# streifen.net
KiCad netlist of a schematic drawn in EAGLE
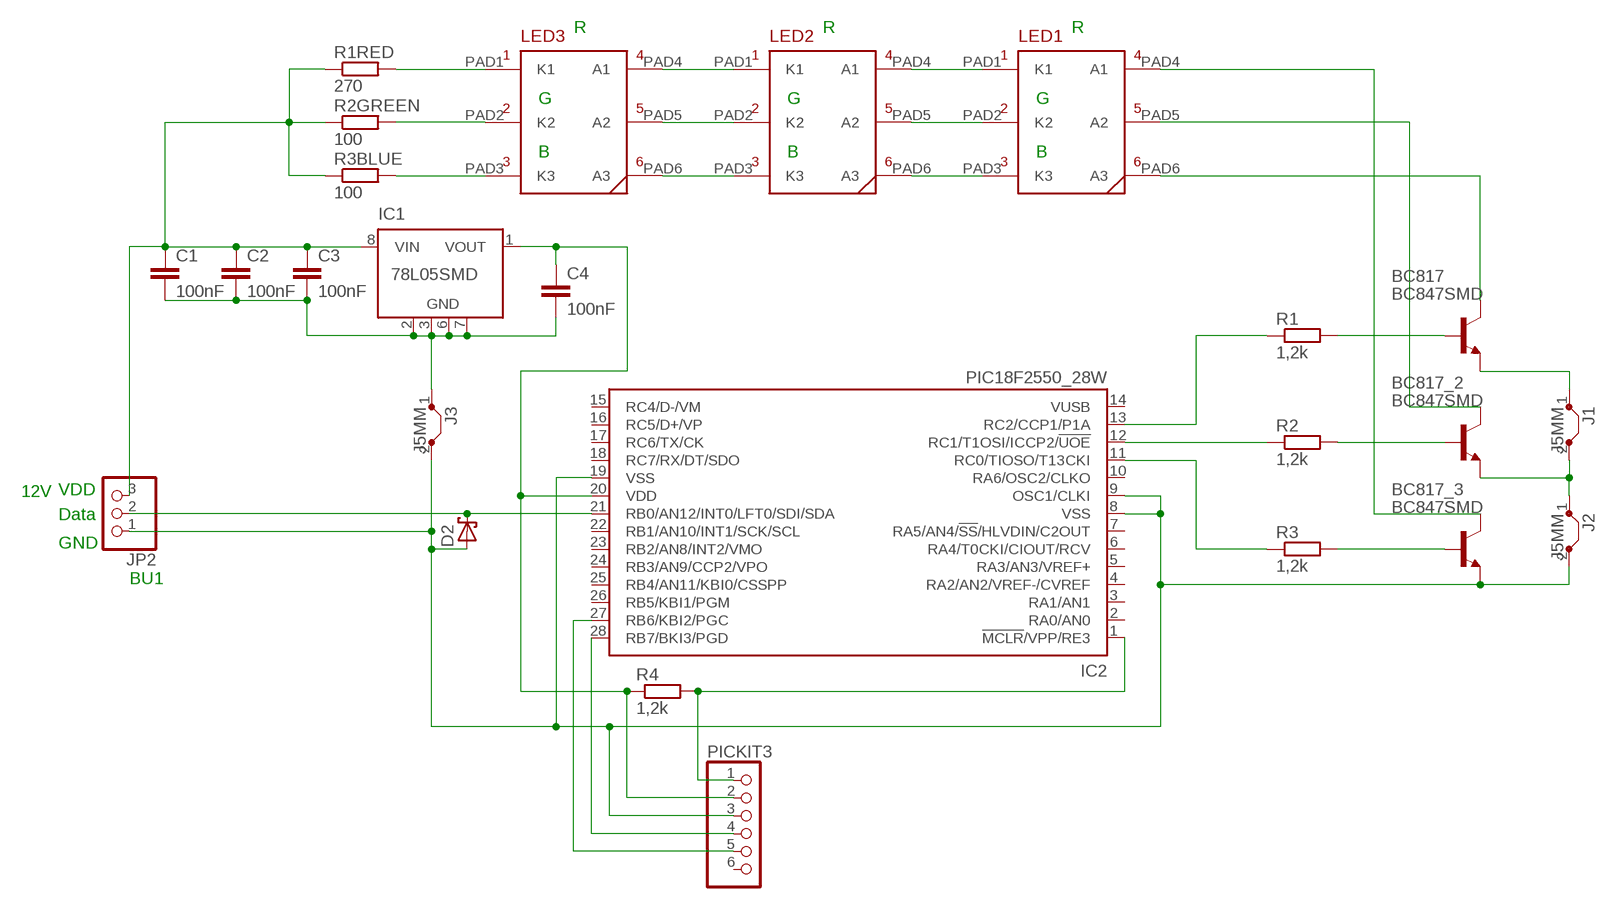
[diagram p0: schematic, sheet 1]

(export (version "E")
  (design (tool "Eeschema 10.0.6"))
  (components
    (comp (ref "BC817")
      (value "BC847SMD")
      (footprint "eagle-import:SOT23")
      (libsource (lib "eagle-import") (part "BC847SMD"))
    )
    (comp (ref "BC817_2")
      (value "BC847SMD")
      (footprint "eagle-import:SOT23")
      (libsource (lib "eagle-import") (part "BC847SMD"))
    )
    (comp (ref "BC817_3")
      (value "BC847SMD")
      (footprint "eagle-import:SOT23")
      (libsource (lib "eagle-import") (part "BC847SMD"))
    )
    (comp (ref "C1")
      (value "100nF")
      (footprint "eagle-import:C1206")
      (libsource (lib "eagle-import") (part "C-EUC1206"))
    )
    (comp (ref "C2")
      (value "100nF")
      (footprint "eagle-import:C1206")
      (libsource (lib "eagle-import") (part "C-EUC1206"))
    )
    (comp (ref "C3")
      (value "100nF")
      (footprint "eagle-import:C1206")
      (libsource (lib "eagle-import") (part "C-EUC1206"))
    )
    (comp (ref "C4")
      (value "100nF")
      (footprint "eagle-import:C1206")
      (libsource (lib "eagle-import") (part "C-EUC1206"))
    )
    (comp (ref "D2")
      (value "SCHOTTKY-DIODEDO35-7")
      (footprint "eagle-import:DO35-7")
      (libsource (lib "eagle-import") (part "SCHOTTKY-DIODEDO35-7"))
    )
    (comp (ref "IC1")
      (value "78L05SMD")
      (footprint "eagle-import:SO08")
      (libsource (lib "eagle-import") (part "78LSMD05"))
    )
    (comp (ref "IC2")
      (value "PIC18F2550_28W")
      (footprint "eagle-import:SO28W")
      (fields (field (name "MF") "MICROCHIP") (field (name "MPN") "PIC18F2550-I/SO"))
      (libsource (lib "eagle-import") (part "PIC18F2_28W550"))
    )
    (comp (ref "J1")
      (value "J5MM")
      (footprint "eagle-import:05")
      (libsource (lib "eagle-import") (part "J5MM"))
    )
    (comp (ref "J2")
      (value "J5MM")
      (footprint "eagle-import:05")
      (libsource (lib "eagle-import") (part "J5MM"))
    )
    (comp (ref "J3")
      (value "J5MM")
      (footprint "eagle-import:05")
      (libsource (lib "eagle-import") (part "J5MM"))
    )
    (comp (ref "JP2")
      (value "PINHD-1X3")
      (footprint "eagle-import:1X03")
      (libsource (lib "eagle-import") (part "PINHD-1X3"))
    )
    (comp (ref "LED1")
      (value "LP6-EWN1-03-N3")
      (footprint "eagle-import:PLCC6")
      (libsource (lib "eagle-import") (part "LP6-EWN1-03-N3"))
    )
    (comp (ref "LED2")
      (value "LP6-EWN1-03-N3")
      (footprint "eagle-import:PLCC6")
      (libsource (lib "eagle-import") (part "LP6-EWN1-03-N3"))
    )
    (comp (ref "LED3")
      (value "LP6-EWN1-03-N3")
      (footprint "eagle-import:PLCC6")
      (libsource (lib "eagle-import") (part "LP6-EWN1-03-N3"))
    )
    (comp (ref "PICKIT3")
      (value "PINHD-1X6")
      (footprint "eagle-import:1X06")
      (libsource (lib "eagle-import") (part "PINHD-1X6"))
    )
    (comp (ref "R1")
      (value "1,2k")
      (footprint "eagle-import:R1206")
      (libsource (lib "eagle-import") (part "R-EU_R1206"))
    )
    (comp (ref "R1RED")
      (value "270")
      (footprint "eagle-import:R1206")
      (libsource (lib "eagle-import") (part "R-EU_R1206"))
    )
    (comp (ref "R2")
      (value "1,2k")
      (footprint "eagle-import:R1206")
      (libsource (lib "eagle-import") (part "R-EU_R1206"))
    )
    (comp (ref "R2GREEN")
      (value "100")
      (footprint "eagle-import:R1206")
      (libsource (lib "eagle-import") (part "R-EU_R1206"))
    )
    (comp (ref "R3")
      (value "1,2k")
      (footprint "eagle-import:R1206")
      (libsource (lib "eagle-import") (part "R-EU_R1206"))
    )
    (comp (ref "R3BLUE")
      (value "100")
      (footprint "eagle-import:R1206")
      (libsource (lib "eagle-import") (part "R-EU_R1206"))
    )
    (comp (ref "R4")
      (value "1,2k")
      (footprint "eagle-import:R1206")
      (libsource (lib "eagle-import") (part "R-EU_R1206"))
    )
  )
  (nets
    (net (code "1") (name "/GND") (class "Default")
      (node (ref "BC817_3") (pin "2") (pinfunction "E_2") (pintype "passive"))
      (node (ref "C1") (pin "2") (pinfunction "2_2") (pintype "passive"))
      (node (ref "C2") (pin "2") (pinfunction "2_2") (pintype "passive"))
      (node (ref "C3") (pin "2") (pinfunction "2_2") (pintype "passive"))
      (node (ref "C4") (pin "2") (pinfunction "2_2") (pintype "passive"))
      (node (ref "D2") (pin "A") (pinfunction "A_A") (pintype "passive"))
      (node (ref "IC1") (pin "2") (pinfunction "GND_2") (pintype "power_in"))
      (node (ref "IC1") (pin "3") (pinfunction "GND_3") (pintype "power_in"))
      (node (ref "IC1") (pin "6") (pinfunction "GND_6") (pintype "power_in"))
      (node (ref "IC1") (pin "7") (pinfunction "GND_7") (pintype "power_in"))
      (node (ref "IC2") (pin "19") (pinfunction "VSS_19") (pintype "power_in"))
      (node (ref "IC2") (pin "8") (pinfunction "VSS_8") (pintype "power_in"))
      (node (ref "IC2") (pin "9") (pinfunction "OSC1/CLKI_9") (pintype "input"))
      (node (ref "J2") (pin "2") (pinfunction "2_2") (pintype "passive"))
      (node (ref "J3") (pin "1") (pinfunction "1_1") (pintype "passive"))
      (node (ref "J3") (pin "2") (pinfunction "2_2") (pintype "passive"))
      (node (ref "JP2") (pin "1") (pinfunction "1_1") (pintype "passive"))
      (node (ref "PICKIT3") (pin "3") (pinfunction "3_3") (pintype "passive"))
    )
    (net (code "2") (name "Net-(BC817-B)") (class "Default")
      (node (ref "BC817") (pin "1") (pinfunction "B_1") (pintype "passive"))
      (node (ref "R1") (pin "2") (pinfunction "2_2") (pintype "passive"))
    )
    (net (code "3") (name "Net-(BC817-C)") (class "Default")
      (node (ref "BC817") (pin "3") (pinfunction "C_3") (pintype "passive"))
      (node (ref "LED1") (pin "PAD6") (pinfunction "A3_PAD6") (pintype "input"))
    )
    (net (code "4") (name "Net-(BC817-E)") (class "Default")
      (node (ref "BC817") (pin "2") (pinfunction "E_2") (pintype "passive"))
      (node (ref "J1") (pin "1") (pinfunction "1_1") (pintype "passive"))
    )
    (net (code "5") (name "Net-(BC817_2-B)") (class "Default")
      (node (ref "BC817_2") (pin "1") (pinfunction "B_1") (pintype "passive"))
      (node (ref "R2") (pin "2") (pinfunction "2_2") (pintype "passive"))
    )
    (net (code "6") (name "Net-(BC817_2-C)") (class "Default")
      (node (ref "BC817_2") (pin "3") (pinfunction "C_3") (pintype "passive"))
      (node (ref "LED1") (pin "PAD5") (pinfunction "A2_PAD5") (pintype "input"))
    )
    (net (code "7") (name "Net-(BC817_2-E)") (class "Default")
      (node (ref "BC817_2") (pin "2") (pinfunction "E_2") (pintype "passive"))
      (node (ref "J1") (pin "2") (pinfunction "2_2") (pintype "passive"))
      (node (ref "J2") (pin "1") (pinfunction "1_1") (pintype "passive"))
    )
    (net (code "8") (name "Net-(BC817_3-B)") (class "Default")
      (node (ref "BC817_3") (pin "1") (pinfunction "B_1") (pintype "passive"))
      (node (ref "R3") (pin "2") (pinfunction "2_2") (pintype "passive"))
    )
    (net (code "9") (name "Net-(BC817_3-C)") (class "Default")
      (node (ref "BC817_3") (pin "3") (pinfunction "C_3") (pintype "passive"))
      (node (ref "LED1") (pin "PAD4") (pinfunction "A1_PAD4") (pintype "input"))
    )
    (net (code "10") (name "Net-(IC1A-VIN)") (class "Default")
      (node (ref "C1") (pin "1") (pinfunction "1_1") (pintype "passive"))
      (node (ref "C2") (pin "1") (pinfunction "1_1") (pintype "passive"))
      (node (ref "C3") (pin "1") (pinfunction "1_1") (pintype "passive"))
      (node (ref "IC1") (pin "8") (pinfunction "VIN_8") (pintype "passive"))
      (node (ref "JP2") (pin "3") (pinfunction "3_3") (pintype "passive"))
      (node (ref "R1RED") (pin "1") (pinfunction "1_1") (pintype "passive"))
      (node (ref "R2GREEN") (pin "1") (pinfunction "1_1") (pintype "passive"))
      (node (ref "R3BLUE") (pin "1") (pinfunction "1_1") (pintype "passive"))
    )
    (net (code "11") (name "Net-(IC1A-VOUT)") (class "Default")
      (node (ref "C4") (pin "1") (pinfunction "1_1") (pintype "passive"))
      (node (ref "IC1") (pin "1") (pinfunction "VOUT_1") (pintype "output"))
      (node (ref "IC2") (pin "20") (pinfunction "VDD_20") (pintype "power_in"))
      (node (ref "PICKIT3") (pin "2") (pinfunction "2_2") (pintype "passive"))
      (node (ref "R4") (pin "1") (pinfunction "1_1") (pintype "passive"))
    )
    (net (code "12") (name "Net-(IC2-RB0{slash}AN12{slash}INT0{slash}LFT0{slash}SDI{slash}SDA)") (class "Default")
      (node (ref "D2") (pin "C") (pinfunction "C_C") (pintype "passive"))
      (node (ref "IC2") (pin "21") (pinfunction "RB0/AN12/INT0/LFT0/SDI/SDA_21") (pintype "bidirectional"))
      (node (ref "JP2") (pin "2") (pinfunction "2_2") (pintype "passive"))
    )
    (net (code "13") (name "Net-(IC2-RB6{slash}KBI2{slash}PGC)") (class "Default")
      (node (ref "IC2") (pin "27") (pinfunction "RB6/KBI2/PGC_27") (pintype "bidirectional"))
      (node (ref "PICKIT3") (pin "5") (pinfunction "5_5") (pintype "passive"))
    )
    (net (code "14") (name "Net-(IC2-RB7{slash}BKI3{slash}PGD)") (class "Default")
      (node (ref "IC2") (pin "28") (pinfunction "RB7/BKI3/PGD_28") (pintype "bidirectional"))
      (node (ref "PICKIT3") (pin "4") (pinfunction "4_4") (pintype "passive"))
    )
    (net (code "15") (name "Net-(IC2-RC0{slash}TIOSO{slash}T13CKI)") (class "Default")
      (node (ref "IC2") (pin "11") (pinfunction "RC0/TIOSO/T13CKI_11") (pintype "bidirectional"))
      (node (ref "R3") (pin "1") (pinfunction "1_1") (pintype "passive"))
    )
    (net (code "16") (name "Net-(IC2-RC1{slash}T1OSI{slash}ICCP2{slash}~{UOE})") (class "Default")
      (node (ref "IC2") (pin "12") (pinfunction "RC1/T1OSI/ICCP2/~{UOE}_12") (pintype "bidirectional"))
      (node (ref "R2") (pin "1") (pinfunction "1_1") (pintype "passive"))
    )
    (net (code "17") (name "Net-(IC2-RC2{slash}CCP1{slash}P1A)") (class "Default")
      (node (ref "IC2") (pin "13") (pinfunction "RC2/CCP1/P1A_13") (pintype "bidirectional"))
      (node (ref "R1") (pin "1") (pinfunction "1_1") (pintype "passive"))
    )
    (net (code "18") (name "Net-(IC2-~{MCLR}{slash}VPP{slash}RE3)") (class "Default")
      (node (ref "IC2") (pin "1") (pinfunction "~{MCLR}/VPP/RE3_1") (pintype "input"))
      (node (ref "PICKIT3") (pin "1") (pinfunction "1_1") (pintype "passive"))
      (node (ref "R4") (pin "2") (pinfunction "2_2") (pintype "passive"))
    )
    (net (code "19") (name "Net-(LED1-K1)") (class "Default")
      (node (ref "LED1") (pin "PAD1") (pinfunction "K1_PAD1") (pintype "output"))
      (node (ref "LED2") (pin "PAD4") (pinfunction "A1_PAD4") (pintype "input"))
    )
    (net (code "20") (name "Net-(LED1-K2)") (class "Default")
      (node (ref "LED1") (pin "PAD2") (pinfunction "K2_PAD2") (pintype "output"))
      (node (ref "LED2") (pin "PAD5") (pinfunction "A2_PAD5") (pintype "input"))
    )
    (net (code "21") (name "Net-(LED1-K3)") (class "Default")
      (node (ref "LED1") (pin "PAD3") (pinfunction "K3_PAD3") (pintype "output"))
      (node (ref "LED2") (pin "PAD6") (pinfunction "A3_PAD6") (pintype "input"))
    )
    (net (code "22") (name "Net-(LED2-K1)") (class "Default")
      (node (ref "LED2") (pin "PAD1") (pinfunction "K1_PAD1") (pintype "output"))
      (node (ref "LED3") (pin "PAD4") (pinfunction "A1_PAD4") (pintype "input"))
    )
    (net (code "23") (name "Net-(LED2-K2)") (class "Default")
      (node (ref "LED2") (pin "PAD2") (pinfunction "K2_PAD2") (pintype "output"))
      (node (ref "LED3") (pin "PAD5") (pinfunction "A2_PAD5") (pintype "input"))
    )
    (net (code "24") (name "Net-(LED2-K3)") (class "Default")
      (node (ref "LED2") (pin "PAD3") (pinfunction "K3_PAD3") (pintype "output"))
      (node (ref "LED3") (pin "PAD6") (pinfunction "A3_PAD6") (pintype "input"))
    )
    (net (code "25") (name "Net-(LED3-K1)") (class "Default")
      (node (ref "LED3") (pin "PAD1") (pinfunction "K1_PAD1") (pintype "output"))
      (node (ref "R1RED") (pin "2") (pinfunction "2_2") (pintype "passive"))
    )
    (net (code "26") (name "Net-(LED3-K2)") (class "Default")
      (node (ref "LED3") (pin "PAD2") (pinfunction "K2_PAD2") (pintype "output"))
      (node (ref "R2GREEN") (pin "2") (pinfunction "2_2") (pintype "passive"))
    )
    (net (code "27") (name "Net-(LED3-K3)") (class "Default")
      (node (ref "LED3") (pin "PAD3") (pinfunction "K3_PAD3") (pintype "output"))
      (node (ref "R3BLUE") (pin "2") (pinfunction "2_2") (pintype "passive"))
    )
    (net (code "28") (name "unconnected-(IC2-RA0{slash}AN0-Pad2)") (class "Default")
      (node (ref "IC2") (pin "2") (pinfunction "RA0/AN0_2") (pintype "bidirectional"))
    )
    (net (code "29") (name "unconnected-(IC2-RA1{slash}AN1-Pad3)") (class "Default")
      (node (ref "IC2") (pin "3") (pinfunction "RA1/AN1_3") (pintype "bidirectional"))
    )
    (net (code "30") (name "unconnected-(IC2-RA2{slash}AN2{slash}VREF-{slash}CVREF-Pad4)") (class "Default")
      (node (ref "IC2") (pin "4") (pinfunction "RA2/AN2/VREF-/CVREF_4") (pintype "bidirectional"))
    )
    (net (code "31") (name "unconnected-(IC2-RA3{slash}AN3{slash}VREF+-Pad5)") (class "Default")
      (node (ref "IC2") (pin "5") (pinfunction "RA3/AN3/VREF+_5") (pintype "bidirectional"))
    )
    (net (code "32") (name "unconnected-(IC2-RA4{slash}T0CKI{slash}CIOUT{slash}RCV-Pad6)") (class "Default")
      (node (ref "IC2") (pin "6") (pinfunction "RA4/T0CKI/CIOUT/RCV_6") (pintype "bidirectional"))
    )
    (net (code "33") (name "unconnected-(IC2-RA5{slash}AN4{slash}~{SS}{slash}HLVDIN{slash}C2OUT-Pad7)") (class "Default")
      (node (ref "IC2") (pin "7") (pinfunction "RA5/AN4/~{SS}/HLVDIN/C2OUT_7") (pintype "bidirectional"))
    )
    (net (code "34") (name "unconnected-(IC2-RA6{slash}OSC2{slash}CLKO-Pad10)") (class "Default")
      (node (ref "IC2") (pin "10") (pinfunction "RA6/OSC2/CLKO_10") (pintype "output"))
    )
    (net (code "35") (name "unconnected-(IC2-RB1{slash}AN10{slash}INT1{slash}SCK{slash}SCL-Pad22)") (class "Default")
      (node (ref "IC2") (pin "22") (pinfunction "RB1/AN10/INT1/SCK/SCL_22") (pintype "bidirectional"))
    )
    (net (code "36") (name "unconnected-(IC2-RB2{slash}AN8{slash}INT2{slash}VMO-Pad23)") (class "Default")
      (node (ref "IC2") (pin "23") (pinfunction "RB2/AN8/INT2/VMO_23") (pintype "bidirectional"))
    )
    (net (code "37") (name "unconnected-(IC2-RB3{slash}AN9{slash}CCP2{slash}VPO-Pad24)") (class "Default")
      (node (ref "IC2") (pin "24") (pinfunction "RB3/AN9/CCP2/VPO_24") (pintype "bidirectional"))
    )
    (net (code "38") (name "unconnected-(IC2-RB4{slash}AN11{slash}KBI0{slash}CSSPP-Pad25)") (class "Default")
      (node (ref "IC2") (pin "25") (pinfunction "RB4/AN11/KBI0/CSSPP_25") (pintype "bidirectional"))
    )
    (net (code "39") (name "unconnected-(IC2-RB5{slash}KBI1{slash}PGM-Pad26)") (class "Default")
      (node (ref "IC2") (pin "26") (pinfunction "RB5/KBI1/PGM_26") (pintype "bidirectional"))
    )
    (net (code "40") (name "unconnected-(IC2-RC4{slash}D-{slash}VM-Pad15)") (class "Default")
      (node (ref "IC2") (pin "15") (pinfunction "RC4/D-/VM_15") (pintype "bidirectional"))
    )
    (net (code "41") (name "unconnected-(IC2-RC5{slash}D+{slash}VP-Pad16)") (class "Default")
      (node (ref "IC2") (pin "16") (pinfunction "RC5/D+/VP_16") (pintype "bidirectional"))
    )
    (net (code "42") (name "unconnected-(IC2-RC6{slash}TX{slash}CK-Pad17)") (class "Default")
      (node (ref "IC2") (pin "17") (pinfunction "RC6/TX/CK_17") (pintype "bidirectional"))
    )
    (net (code "43") (name "unconnected-(IC2-RC7{slash}RX{slash}DT{slash}SDO-Pad18)") (class "Default")
      (node (ref "IC2") (pin "18") (pinfunction "RC7/RX/DT/SDO_18") (pintype "bidirectional"))
    )
    (net (code "44") (name "unconnected-(IC2-VUSB-Pad14)") (class "Default")
      (node (ref "IC2") (pin "14") (pinfunction "VUSB_14") (pintype "bidirectional"))
    )
    (net (code "45") (name "unconnected-(PICKIT3-Pad6)") (class "Default")
      (node (ref "PICKIT3") (pin "6") (pinfunction "6_6") (pintype "passive"))
    )
  )
)
